# qtpychargerpzt3904.net
KiCad netlist of a schematic drawn in EAGLE
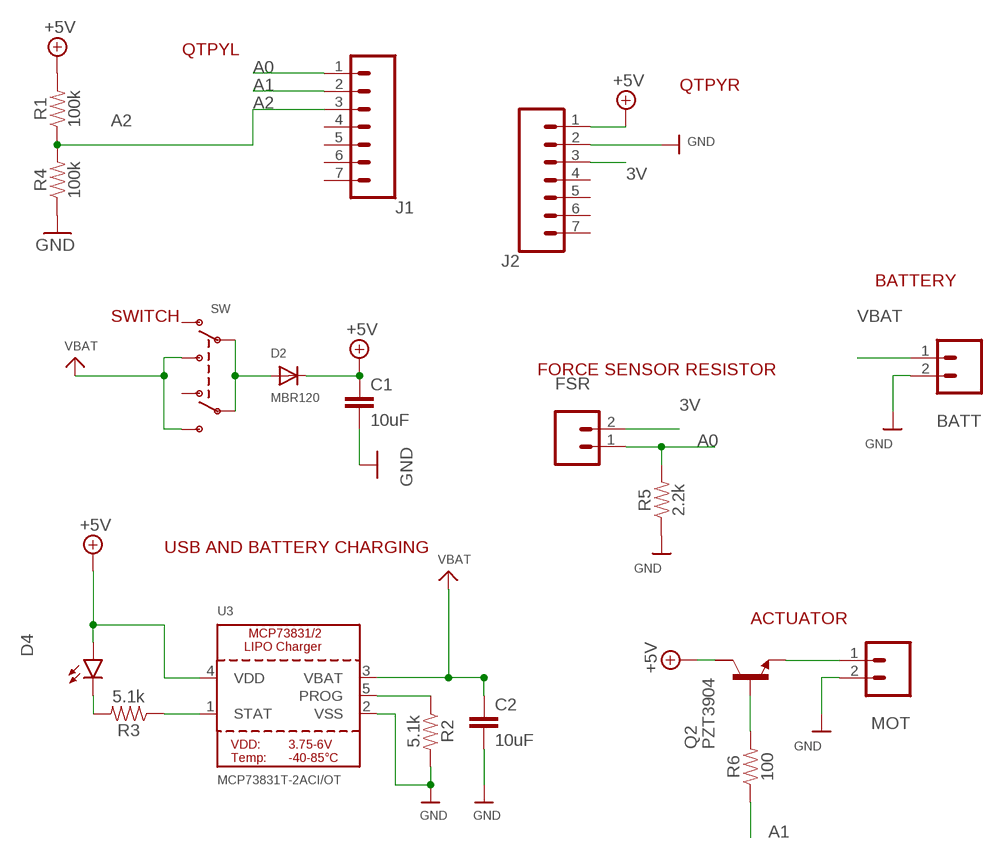
[diagram p0: schematic, sheet 1]

(export (version "E")
  (design (tool "Eeschema 10.0.6"))
  (components
    (comp (ref "BATT")
      (value "CONN_02")
      (footprint "eagle-import:1X02")
      (libsource (lib "eagle-import") (part "CONN_02"))
    )
    (comp (ref "C1")
      (value "10uF")
      (footprint "eagle-import:1206")
      (libsource (lib "eagle-import") (part "10UF-1206-6.3V-20%"))
    )
    (comp (ref "C2")
      (value "10uF")
      (footprint "eagle-import:1206")
      (libsource (lib "eagle-import") (part "10UF-1206-6.3V-20%"))
    )
    (comp (ref "D2")
      (value "MBR120")
      (footprint "eagle-import:SOD-123FL")
      (libsource (lib "eagle-import") (part "DIODE_SOD-123FL"))
    )
    (comp (ref "D4")
      (value "LED1206")
      (footprint "eagle-import:LED-1206")
      (libsource (lib "eagle-import") (part "LED1206"))
    )
    (comp (ref "FSR")
      (value "CONN_02")
      (footprint "eagle-import:1X02")
      (libsource (lib "eagle-import") (part "CONN_02"))
    )
    (comp (ref "J1")
      (value "CONN_07")
      (footprint "eagle-import:1X07")
      (libsource (lib "eagle-import") (part "CONN_07"))
    )
    (comp (ref "J2")
      (value "CONN_07")
      (footprint "eagle-import:1X07")
      (libsource (lib "eagle-import") (part "CONN_07"))
    )
    (comp (ref "MOT")
      (value "CONN_02")
      (footprint "eagle-import:1X02")
      (libsource (lib "eagle-import") (part "CONN_02"))
    )
    (comp (ref "Q2")
      (value "PZT3904")
      (footprint "eagle-import:SOT223")
      (fields (field (name "MF") "ON Semiconductor"))
      (libsource (lib "eagle-import") (part "PZT3904"))
    )
    (comp (ref "R1")
      (value "100k")
      (footprint "eagle-import:1206")
      (libsource (lib "eagle-import") (part "RESISTOR1206"))
    )
    (comp (ref "R2")
      (value "5.1k")
      (footprint "eagle-import:1206")
      (libsource (lib "eagle-import") (part "RESISTOR1206"))
    )
    (comp (ref "R3")
      (value "5.1k")
      (footprint "eagle-import:1206")
      (libsource (lib "eagle-import") (part "RESISTOR1206"))
    )
    (comp (ref "R4")
      (value "100k")
      (footprint "eagle-import:1206")
      (libsource (lib "eagle-import") (part "RESISTOR1206"))
    )
    (comp (ref "R5")
      (value "2.2k")
      (footprint "eagle-import:1206")
      (libsource (lib "eagle-import") (part "RESISTOR1206"))
    )
    (comp (ref "R6")
      (value "100")
      (footprint "eagle-import:1206")
      (libsource (lib "eagle-import") (part "RESISTOR1206"))
    )
    (comp (ref "SW")
      (value "SWITCH_DPDTEG1390")
      (footprint "eagle-import:EG1390")
      (libsource (lib "eagle-import") (part "SWITCH_DPDTEG1390"))
    )
    (comp (ref "U3")
      (value "MCP73831T-2ACI/OT")
      (footprint "eagle-import:SOT23-5")
      (libsource (lib "eagle-import") (part "MCP73831/2"))
    )
  )
  (nets
    (net (code "1") (name "+5V") (class "Default")
      (node (ref "C1") (pin "1") (pinfunction "1_1") (pintype "passive"))
      (node (ref "D2") (pin "C") (pinfunction "C_C") (pintype "passive"))
      (node (ref "D4") (pin "A") (pinfunction "A_A") (pintype "passive"))
      (node (ref "J2") (pin "1") (pinfunction "1_1") (pintype "passive"))
      (node (ref "Q2") (pin "2") (pinfunction "C_2") (pintype "passive"))
      (node (ref "R1") (pin "2") (pinfunction "2_2") (pintype "passive"))
      (node (ref "U3") (pin "4") (pinfunction "VDD_4") (pintype "power_in"))
    )
    (net (code "2") (name "/3V") (class "Default")
      (node (ref "FSR") (pin "2") (pinfunction "2_2") (pintype "passive"))
      (node (ref "J2") (pin "3") (pinfunction "3_3") (pintype "passive"))
    )
    (net (code "3") (name "/A0") (class "Default")
      (node (ref "FSR") (pin "1") (pinfunction "1_1") (pintype "passive"))
      (node (ref "J1") (pin "1") (pinfunction "1_1") (pintype "passive"))
      (node (ref "R5") (pin "2") (pinfunction "2_2") (pintype "passive"))
    )
    (net (code "4") (name "/A1") (class "Default")
      (node (ref "J1") (pin "2") (pinfunction "2_2") (pintype "passive"))
      (node (ref "R6") (pin "1") (pinfunction "1_1") (pintype "passive"))
    )
    (net (code "5") (name "/A2") (class "Default")
      (node (ref "J1") (pin "3") (pinfunction "3_3") (pintype "passive"))
      (node (ref "R1") (pin "1") (pinfunction "1_1") (pintype "passive"))
      (node (ref "R4") (pin "2") (pinfunction "2_2") (pintype "passive"))
    )
    (net (code "6") (name "GND") (class "Default")
      (node (ref "BATT") (pin "2") (pinfunction "2_2") (pintype "passive"))
      (node (ref "C1") (pin "2") (pinfunction "2_2") (pintype "passive"))
      (node (ref "C2") (pin "2") (pinfunction "2_2") (pintype "passive"))
      (node (ref "J2") (pin "2") (pinfunction "2_2") (pintype "passive"))
      (node (ref "MOT") (pin "2") (pinfunction "2_2") (pintype "passive"))
      (node (ref "R2") (pin "2") (pinfunction "2_2") (pintype "passive"))
      (node (ref "R4") (pin "1") (pinfunction "1_1") (pintype "passive"))
      (node (ref "R5") (pin "1") (pinfunction "1_1") (pintype "passive"))
      (node (ref "U3") (pin "2") (pinfunction "VSS_2") (pintype "power_in"))
    )
    (net (code "7") (name "Net-(D2-PadA)") (class "Default")
      (node (ref "D2") (pin "A") (pinfunction "A_A") (pintype "passive"))
      (node (ref "SW") (pin "P1") (pinfunction "P1_P1") (pintype "passive"))
      (node (ref "SW") (pin "P2") (pinfunction "P2_P2") (pintype "passive"))
    )
    (net (code "8") (name "Net-(D4-PadC)") (class "Default")
      (node (ref "D4") (pin "C") (pinfunction "C_C") (pintype "passive"))
      (node (ref "R3") (pin "2") (pinfunction "2_2") (pintype "passive"))
    )
    (net (code "9") (name "Net-(Q2-B)") (class "Default")
      (node (ref "Q2") (pin "1") (pinfunction "B_1") (pintype "passive"))
      (node (ref "R6") (pin "2") (pinfunction "2_2") (pintype "passive"))
    )
    (net (code "10") (name "Net-(Q2-E)") (class "Default")
      (node (ref "MOT") (pin "1") (pinfunction "1_1") (pintype "passive"))
      (node (ref "Q2") (pin "3") (pinfunction "E_3") (pintype "passive"))
    )
    (net (code "11") (name "Net-(U3-PROG)") (class "Default")
      (node (ref "R2") (pin "1") (pinfunction "1_1") (pintype "passive"))
      (node (ref "U3") (pin "5") (pinfunction "PROG_5") (pintype "input"))
    )
    (net (code "12") (name "Net-(U3-STAT)") (class "Default")
      (node (ref "R3") (pin "1") (pinfunction "1_1") (pintype "passive"))
      (node (ref "U3") (pin "1") (pinfunction "STAT_1") (pintype "output"))
    )
    (net (code "13") (name "VBAT") (class "Default")
      (node (ref "BATT") (pin "1") (pinfunction "1_1") (pintype "passive"))
      (node (ref "C2") (pin "1") (pinfunction "1_1") (pintype "passive"))
      (node (ref "SW") (pin "S1") (pinfunction "S1_S1") (pintype "passive"))
      (node (ref "SW") (pin "S2") (pinfunction "S2_S2") (pintype "passive"))
      (node (ref "U3") (pin "3") (pinfunction "VBAT_3") (pintype "power_in"))
    )
    (net (code "14") (name "unconnected-(J1-Pad4)") (class "Default")
      (node (ref "J1") (pin "4") (pinfunction "4_4") (pintype "passive"))
    )
    (net (code "15") (name "unconnected-(J1-Pad5)") (class "Default")
      (node (ref "J1") (pin "5") (pinfunction "5_5") (pintype "passive"))
    )
    (net (code "16") (name "unconnected-(J1-Pad6)") (class "Default")
      (node (ref "J1") (pin "6") (pinfunction "6_6") (pintype "passive"))
    )
    (net (code "17") (name "unconnected-(J1-Pad7)") (class "Default")
      (node (ref "J1") (pin "7") (pinfunction "7_7") (pintype "passive"))
    )
    (net (code "18") (name "unconnected-(J2-Pad4)") (class "Default")
      (node (ref "J2") (pin "4") (pinfunction "4_4") (pintype "passive"))
    )
    (net (code "19") (name "unconnected-(J2-Pad5)") (class "Default")
      (node (ref "J2") (pin "5") (pinfunction "5_5") (pintype "passive"))
    )
    (net (code "20") (name "unconnected-(J2-Pad6)") (class "Default")
      (node (ref "J2") (pin "6") (pinfunction "6_6") (pintype "passive"))
    )
    (net (code "21") (name "unconnected-(J2-Pad7)") (class "Default")
      (node (ref "J2") (pin "7") (pinfunction "7_7") (pintype "passive"))
    )
    (net (code "22") (name "unconnected-(Q2-C-Pad4)") (class "Default")
      (node (ref "Q2") (pin "4") (pinfunction "C_4") (pintype "passive"))
    )
    (net (code "23") (name "unconnected-(SW-PadO1)") (class "Default")
      (node (ref "SW") (pin "O1") (pinfunction "O1_O1") (pintype "passive"))
    )
    (net (code "24") (name "unconnected-(SW-PadO2)") (class "Default")
      (node (ref "SW") (pin "O2") (pinfunction "O2_O2") (pintype "passive"))
    )
  )
)
